# CapteurTemperature.net
KiCad netlist of a schematic drawn in EAGLE
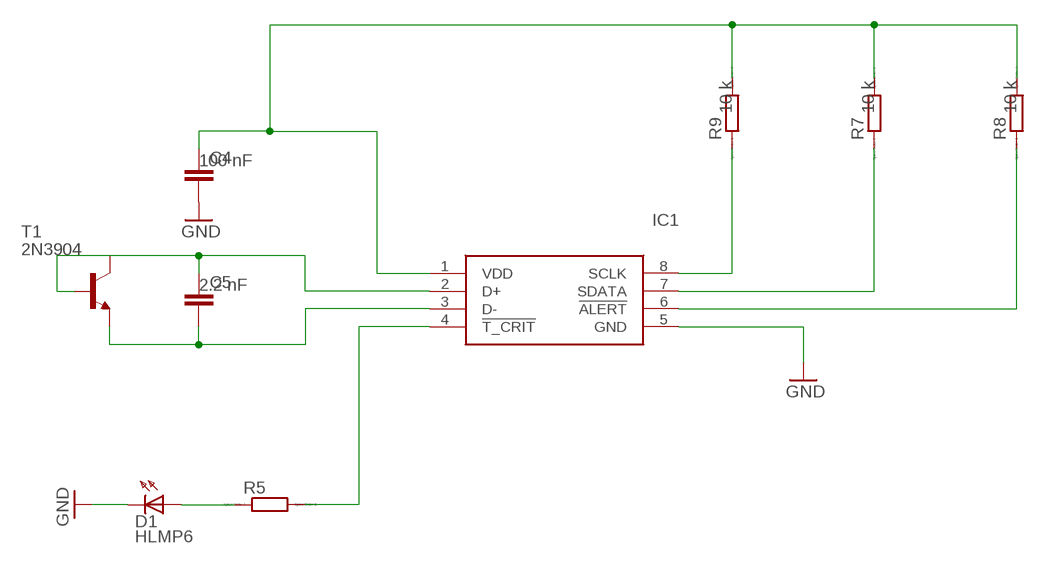
[diagram p0: schematic, sheet 1]

(export (version "E")
  (design (tool "Eeschema 10.0.6"))
  (components
    (comp (ref "C4")
      (value "C-EUC0603")
      (footprint "eagle-import:C0603")
      (fields (field (name "C1") "100 nF"))
      (libsource (lib "eagle-import") (part "C-EUC0603"))
    )
    (comp (ref "C5")
      (value "C-EUC0603")
      (footprint "eagle-import:C0603")
      (fields (field (name "C2") "2.2 nF"))
      (libsource (lib "eagle-import") (part "C-EUC0603"))
    )
    (comp (ref "D1")
      (value "HLMP6")
      (footprint "eagle-import:HLMP6")
      (fields (field (name "MF") "AGILENT TECHNOLOGIES") (field (name "MPN") "HLMP-6500"))
      (libsource (lib "eagle-import") (part "HLMP6"))
    )
    (comp (ref "IC1")
      (value "SA56004AD,118")
      (footprint "eagle-import:SOIC127P600X175-8N")
      (fields (field (name "MOUSER_PART_NUMBER") "771-SA56004AD118"))
      (libsource (lib "eagle-import") (part "SA56004AD,118"))
    )
    (comp (ref "R5")
      (value "RR0603")
      (footprint "eagle-import:R0603")
      (libsource (lib "eagle-import") (part "RR0603"))
    )
    (comp (ref "R7")
      (value "RR0603")
      (footprint "eagle-import:R0603")
      (fields (field (name "R") "10 k"))
      (libsource (lib "eagle-import") (part "RR0603"))
    )
    (comp (ref "R8")
      (value "RR0603")
      (footprint "eagle-import:R0603")
      (fields (field (name "R") "10 k"))
      (libsource (lib "eagle-import") (part "RR0603"))
    )
    (comp (ref "R9")
      (value "RR0603")
      (footprint "eagle-import:R0603")
      (fields (field (name "R") "10 k"))
      (libsource (lib "eagle-import") (part "RR0603"))
    )
    (comp (ref "T1")
      (value "2N3904")
      (footprint "eagle-import:TO92")
      (libsource (lib "eagle-import") (part "2N3904"))
    )
  )
  (nets
    (net (code "1") (name "GND") (class "Default")
      (node (ref "C4") (pin "2") (pinfunction "2_2") (pintype "passive"))
      (node (ref "D1") (pin "K") (pinfunction "K_K") (pintype "passive"))
      (node (ref "IC1") (pin "5") (pinfunction "GND_5") (pintype "bidirectional"))
    )
    (net (code "2") (name "Net-(D1-PadA)") (class "Default")
      (node (ref "D1") (pin "A") (pinfunction "A_A") (pintype "passive"))
      (node (ref "R5") (pin "1") (pinfunction "1_1") (pintype "passive"))
    )
    (net (code "3") (name "Net-(IC1-D+)") (class "Default")
      (node (ref "C5") (pin "1") (pinfunction "1_1") (pintype "passive"))
      (node (ref "IC1") (pin "2") (pinfunction "D+_2") (pintype "bidirectional"))
      (node (ref "T1") (pin "1") (pinfunction "C_1") (pintype "passive"))
      (node (ref "T1") (pin "2") (pinfunction "B_2") (pintype "passive"))
    )
    (net (code "4") (name "Net-(IC1-D-)") (class "Default")
      (node (ref "C5") (pin "2") (pinfunction "2_2") (pintype "passive"))
      (node (ref "IC1") (pin "3") (pinfunction "D-_3") (pintype "bidirectional"))
      (node (ref "T1") (pin "3") (pinfunction "E_3") (pintype "passive"))
    )
    (net (code "5") (name "Net-(IC1-SCLK)") (class "Default")
      (node (ref "IC1") (pin "8") (pinfunction "SCLK_8") (pintype "bidirectional"))
      (node (ref "R9") (pin "1") (pinfunction "1_1") (pintype "passive"))
    )
    (net (code "6") (name "Net-(IC1-SDATA)") (class "Default")
      (node (ref "IC1") (pin "7") (pinfunction "SDATA_7") (pintype "bidirectional"))
      (node (ref "R7") (pin "1") (pinfunction "1_1") (pintype "passive"))
    )
    (net (code "7") (name "Net-(IC1-VDD)") (class "Default")
      (node (ref "C4") (pin "1") (pinfunction "1_1") (pintype "passive"))
      (node (ref "IC1") (pin "1") (pinfunction "VDD_1") (pintype "bidirectional"))
      (node (ref "R7") (pin "2") (pinfunction "2_2") (pintype "passive"))
      (node (ref "R8") (pin "2") (pinfunction "2_2") (pintype "passive"))
      (node (ref "R9") (pin "2") (pinfunction "2_2") (pintype "passive"))
    )
    (net (code "8") (name "Net-(IC1-~{ALERT})") (class "Default")
      (node (ref "IC1") (pin "6") (pinfunction "~{ALERT}_6") (pintype "bidirectional"))
      (node (ref "R8") (pin "1") (pinfunction "1_1") (pintype "passive"))
    )
    (net (code "9") (name "Net-(IC1-~{T_CRIT})") (class "Default")
      (node (ref "IC1") (pin "4") (pinfunction "~{T_CRIT}_4") (pintype "bidirectional"))
      (node (ref "R5") (pin "2") (pinfunction "2_2") (pintype "passive"))
    )
  )
)
